# CC2652RMCURadio.net
KiCad netlist of a schematic drawn in Altium Designer
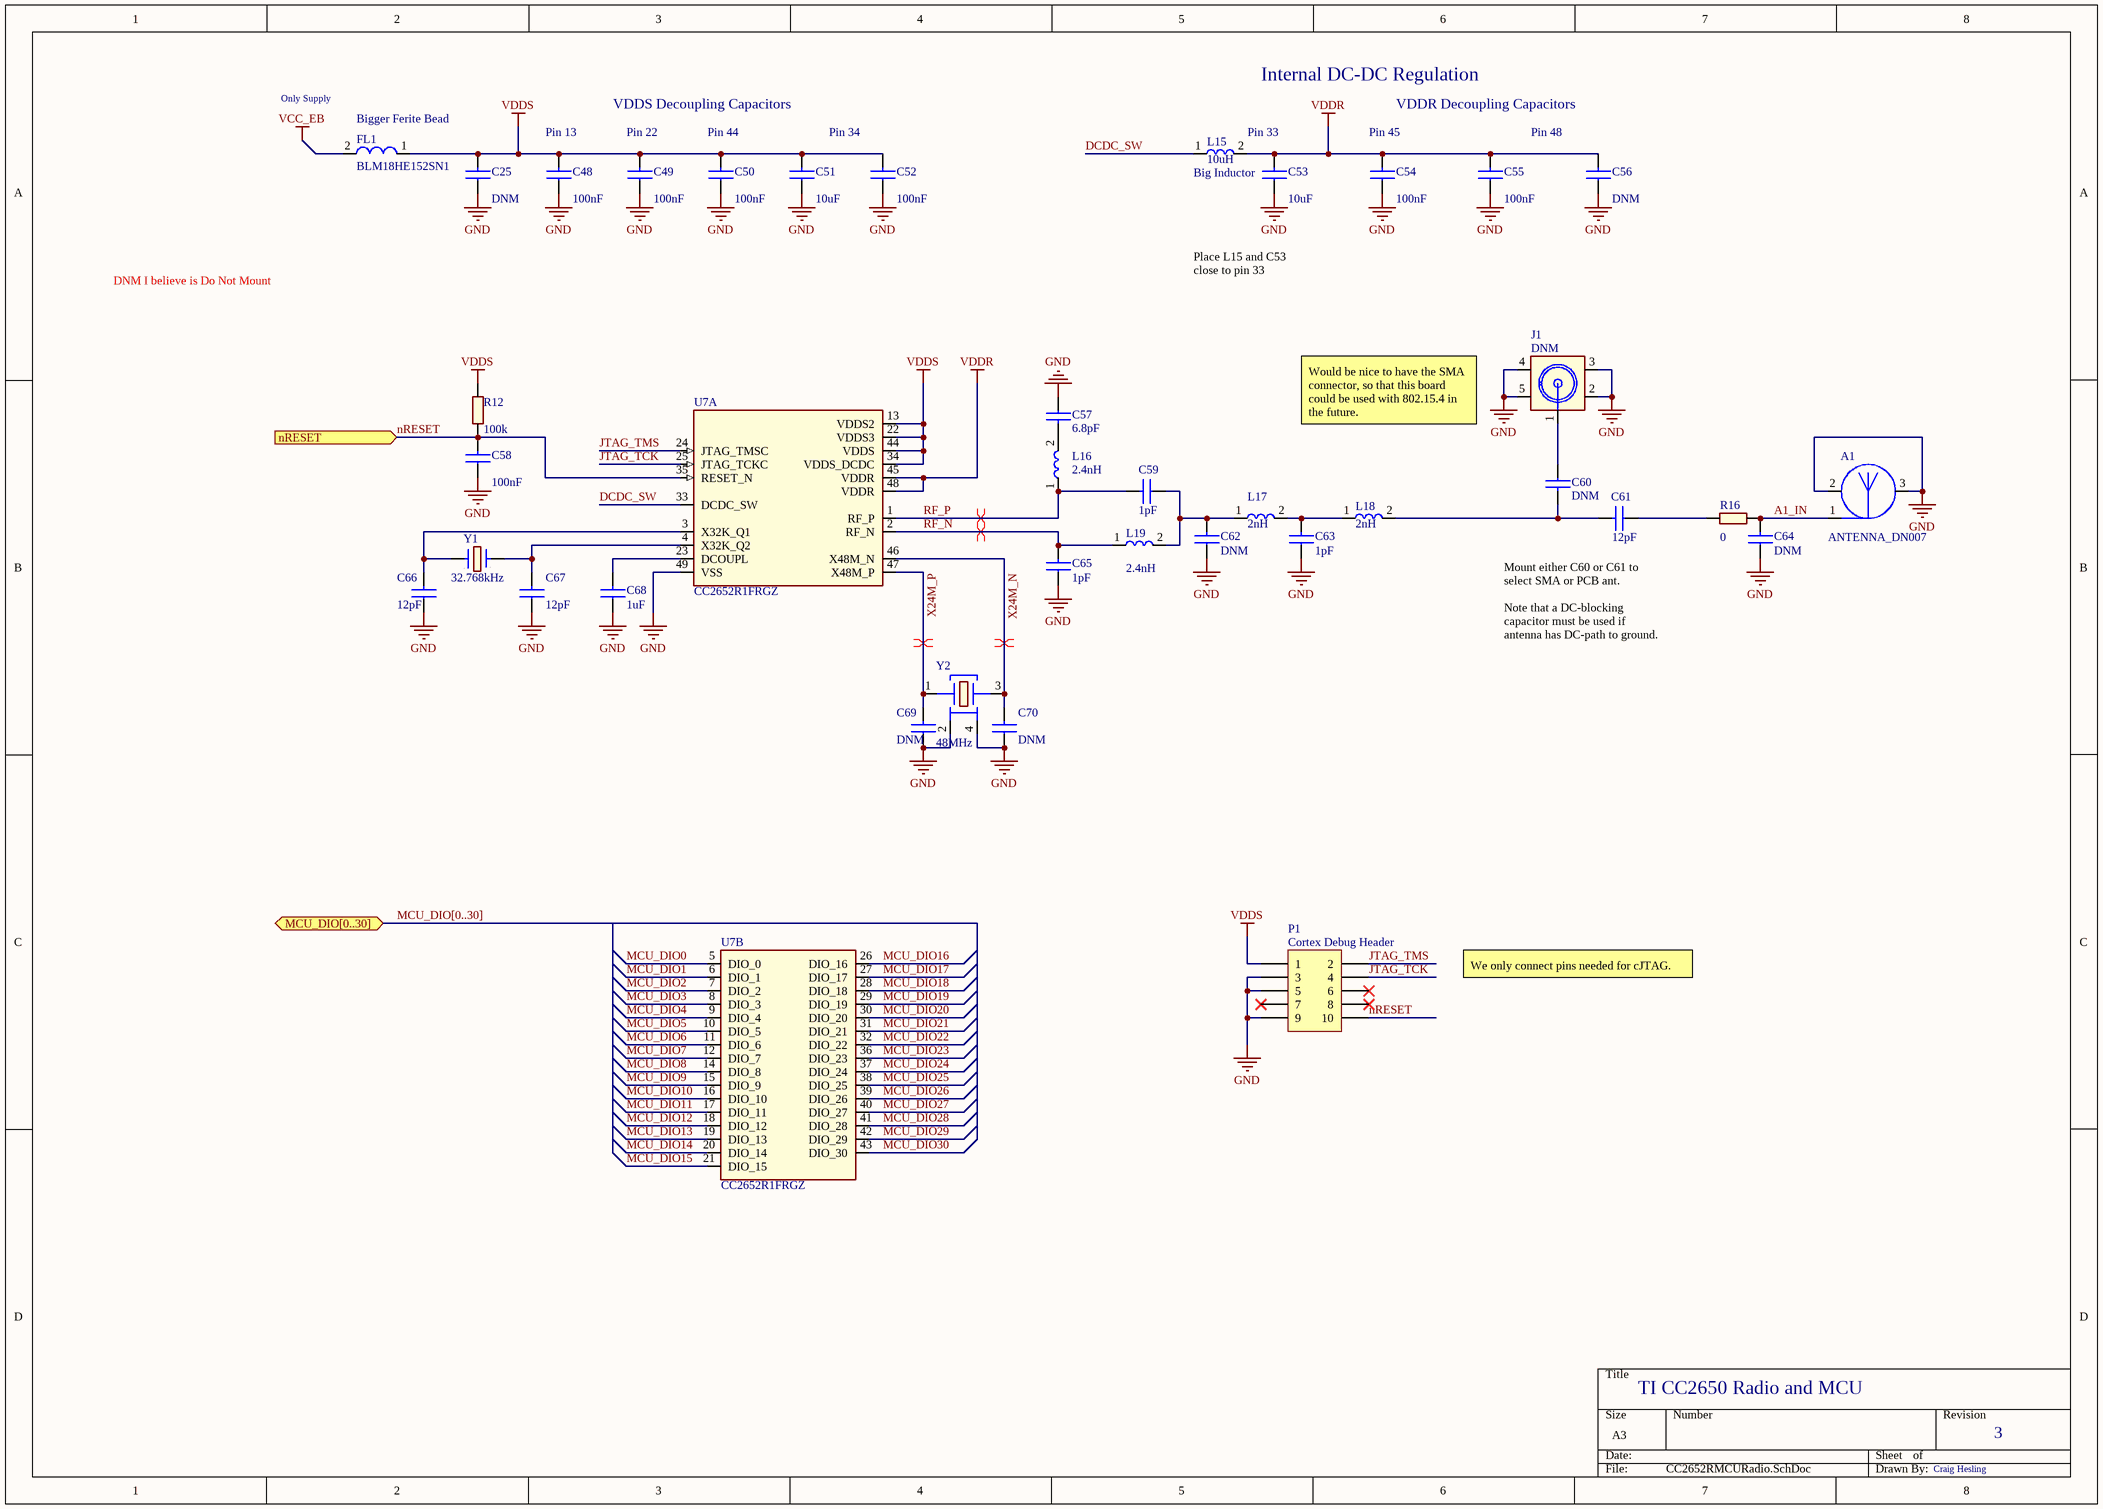
[diagram p0: CC2652RMCURadio.SchDoc]

(export (version "E")
  (design (tool "Eeschema 10.0.6"))
  (components
    (comp (ref "A1")
      (value "ANTENNA_DN007")
      (footprint "ANTENNA_DN007AN_NO_MASK")
      (fields (field (name "DESIGNED BY") "Artur Bielinski"))
      (libsource (lib "CC26XX_7X7_DIFF_Library") (part "ANTENNA_DN007"))
    )
    (comp (ref "C25")
      (value "DNM")
      (footprint "CAPC0402(1005)60_N")
      (fields (field (name "VOLTAGE") "CMAX") (field (name "Comment") "CAPACITOR"))
      (libsource (lib "CC26XX_7X7_DIFF_Library") (part "CAPACITOR"))
    )
    (comp (ref "C48")
      (value "100nF")
      (footprint "CAPC0402(1005)60_N")
      (fields (field (name "VOLTAGE") "CMAX") (field (name "Comment") "CAPACITOR"))
      (libsource (lib "CC26XX_7X7_DIFF_Library") (part "CAPACITOR"))
    )
    (comp (ref "C49")
      (value "100nF")
      (footprint "CAPC0402(1005)60_N")
      (fields (field (name "VOLTAGE") "CMAX") (field (name "Comment") "CAPACITOR"))
      (libsource (lib "CC26XX_7X7_DIFF_Library") (part "CAPACITOR"))
    )
    (comp (ref "C50")
      (value "100nF")
      (footprint "CAPC0402(1005)60_N")
      (fields (field (name "VOLTAGE") "CMAX") (field (name "Comment") "CAPACITOR"))
      (libsource (lib "CC26XX_7X7_DIFF_Library") (part "CAPACITOR"))
    )
    (comp (ref "C51")
      (value "10uF")
      (footprint "CAPC0603(1608)100_N")
      (fields (field (name "VOLTAGE") "CMAX") (field (name "Comment") "CAPACITOR"))
      (libsource (lib "CC26XX_7X7_DIFF_Library") (part "CAPACITOR"))
    )
    (comp (ref "C52")
      (value "100nF")
      (footprint "CAPC0603(1608)100_N")
      (fields (field (name "VOLTAGE") "CMAX") (field (name "Comment") "CAPACITOR"))
      (libsource (lib "CC26XX_7X7_DIFF_Library") (part "CAPACITOR"))
    )
    (comp (ref "C53")
      (value "10uF")
      (footprint "CAPC0603(1608)100_N")
      (fields (field (name "VOLTAGE") "CMAX") (field (name "Comment") "CAPACITOR"))
      (libsource (lib "CC26XX_7X7_DIFF_Library") (part "CAPACITOR"))
    )
    (comp (ref "C54")
      (value "100nF")
      (footprint "CAPC0402(1005)60_N")
      (fields (field (name "VOLTAGE") "CMAX") (field (name "Comment") "CAPACITOR"))
      (libsource (lib "CC26XX_7X7_DIFF_Library") (part "CAPACITOR"))
    )
    (comp (ref "C55")
      (value "100nF")
      (footprint "CAPC0402(1005)60_N")
      (fields (field (name "VOLTAGE") "CMAX") (field (name "Comment") "CAPACITOR"))
      (libsource (lib "CC26XX_7X7_DIFF_Library") (part "CAPACITOR"))
    )
    (comp (ref "C56")
      (value "DNM")
      (footprint "CAPC0402(1005)60_N")
      (fields (field (name "VOLTAGE") "CMAX") (field (name "Comment") "CAPACITOR"))
      (libsource (lib "CC26XX_7X7_DIFF_Library") (part "CAPACITOR"))
    )
    (comp (ref "C57")
      (value "6.8pF")
      (footprint "CAPC0402(1005)60_N")
      (fields (field (name "VOLTAGE") "CMAX") (field (name "Comment") "CAPACITOR"))
      (libsource (lib "CC26XX_7X7_DIFF_Library") (part "CAPACITOR"))
    )
    (comp (ref "C58")
      (value "100nF")
      (footprint "CAPC0402(1005)60_N")
      (fields (field (name "VOLTAGE") "CMAX") (field (name "Comment") "CAPACITOR"))
      (libsource (lib "CC26XX_7X7_DIFF_Library") (part "CAPACITOR"))
    )
    (comp (ref "C59")
      (value "1pF")
      (footprint "CAPC0402(1005)60_N")
      (fields (field (name "VOLTAGE") "CMAX") (field (name "Comment") "CAPACITOR"))
      (libsource (lib "CC26XX_7X7_DIFF_Library") (part "CAPACITOR"))
    )
    (comp (ref "C60")
      (value "DNM")
      (footprint "CAPC0402(1005)60_N")
      (fields (field (name "VOLTAGE") "CMAX") (field (name "Comment") "CAPACITOR"))
      (libsource (lib "CC26XX_7X7_DIFF_Library") (part "CAPACITOR"))
    )
    (comp (ref "C61")
      (value "12pF")
      (footprint "CAPC0402(1005)60_N")
      (fields (field (name "VOLTAGE") "CMAX") (field (name "Comment") "CAPACITOR"))
      (libsource (lib "CC26XX_7X7_DIFF_Library") (part "CAPACITOR"))
    )
    (comp (ref "C62")
      (value "DNM")
      (footprint "CAPC0402(1005)60_N")
      (fields (field (name "VOLTAGE") "CMAX") (field (name "Comment") "CAPACITOR"))
      (libsource (lib "CC26XX_7X7_DIFF_Library") (part "CAPACITOR"))
    )
    (comp (ref "C63")
      (value "1pF")
      (footprint "CAPC0402(1005)60_N")
      (fields (field (name "VOLTAGE") "CMAX") (field (name "Comment") "CAPACITOR"))
      (libsource (lib "CC26XX_7X7_DIFF_Library") (part "CAPACITOR"))
    )
    (comp (ref "C64")
      (value "DNM")
      (footprint "CAPC0402(1005)60_N")
      (fields (field (name "VOLTAGE") "CMAX") (field (name "Comment") "CAPACITOR"))
      (libsource (lib "CC26XX_7X7_DIFF_Library") (part "CAPACITOR"))
    )
    (comp (ref "C65")
      (value "1pF")
      (footprint "CAPC0402(1005)60_N")
      (fields (field (name "VOLTAGE") "CMAX") (field (name "Comment") "CAPACITOR"))
      (libsource (lib "CC26XX_7X7_DIFF_Library") (part "CAPACITOR"))
    )
    (comp (ref "C66")
      (value "12pF")
      (footprint "CAPC0402(1005)60_N")
      (fields (field (name "VOLTAGE") "CMAX") (field (name "Comment") "CAPACITOR"))
      (libsource (lib "CC26XX_7X7_DIFF_Library") (part "CAPACITOR"))
    )
    (comp (ref "C67")
      (value "12pF")
      (footprint "CAPC0402(1005)60_N")
      (fields (field (name "VOLTAGE") "CMAX") (field (name "Comment") "CAPACITOR"))
      (libsource (lib "CC26XX_7X7_DIFF_Library") (part "CAPACITOR"))
    )
    (comp (ref "C68")
      (value "1uF")
      (footprint "CAPC0402(1005)60_N")
      (fields (field (name "VOLTAGE") "CMAX") (field (name "Comment") "CAPACITOR"))
      (libsource (lib "CC26XX_7X7_DIFF_Library") (part "CAPACITOR"))
    )
    (comp (ref "C69")
      (value "DNM")
      (footprint "CAPC0402(1005)60_N")
      (fields (field (name "VOLTAGE") "CMAX") (field (name "Comment") "CAPACITOR"))
      (libsource (lib "CC26XX_7X7_DIFF_Library") (part "CAPACITOR"))
    )
    (comp (ref "C70")
      (value "DNM")
      (footprint "CAPC0402(1005)60_N")
      (fields (field (name "VOLTAGE") "CMAX") (field (name "Comment") "CAPACITOR"))
      (libsource (lib "CC26XX_7X7_DIFF_Library") (part "CAPACITOR"))
    )
    (comp (ref "FL1")
      (value "BLM18HE152SN1")
      (footprint "FIL_BLM18HE152SN1DL")
      (libsource (lib "CC26XX_7X7_DIFF_Library") (part "FILTER_2PIN"))
    )
    (comp (ref "J1")
      (value "DNM")
      (footprint "HUSTSAN_SMA10V21TGGAN_POLYGONPOUR_CUTOUT")
      (libsource (lib "CC26XX_7X7_DIFF_Library") (part "CONN_COAX_1+4"))
    )
    (comp (ref "L15")
      (value "10uH")
      (footprint "CAPC0805(2012)75_N")
      (fields (field (name "Comment") "INDUCTOR"))
      (libsource (lib "CC26XX_7X7_DIFF_Library") (part "INDUCTOR"))
    )
    (comp (ref "L16")
      (value "2.4nH")
      (footprint "INDC1005X60L")
      (fields (field (name "Comment") "INDUCTOR"))
      (libsource (lib "CC26XX_7X7_DIFF_Library") (part "INDUCTOR"))
    )
    (comp (ref "L17")
      (value "2nH")
      (footprint "INDC1005X60L")
      (fields (field (name "Comment") "INDUCTOR"))
      (libsource (lib "CC26XX_7X7_DIFF_Library") (part "INDUCTOR"))
    )
    (comp (ref "L18")
      (value "2nH")
      (footprint "INDC1005X60L")
      (fields (field (name "Comment") "INDUCTOR"))
      (libsource (lib "CC26XX_7X7_DIFF_Library") (part "INDUCTOR"))
    )
    (comp (ref "L19")
      (value "2.4nH")
      (footprint "INDC1005X60L")
      (fields (field (name "Comment") "INDUCTOR"))
      (libsource (lib "CC26XX_7X7_DIFF_Library") (part "INDUCTOR"))
    )
    (comp (ref "P1")
      (value "Cortex Debug Header")
      (footprint "Header 1.27mm 2x5 SMT Low-Profile")
      (description "Header 1.27mm 5X2 SMT Low-Profile")
      (fields (field (name "PUBLISHER") "Altium Limited"))
      (libsource (lib "Connectors") (part "Header 1.27mm 5X2 SMT Low-Profile"))
    )
    (comp (ref "R12")
      (value "100k")
      (footprint "RESC1005X40L")
      (fields
        (field (name "VOLTAGE") "RVMAX")
        (field (name "POWER") "RMAX")
        (field (name "Comment") "RESISTOR")
      )
      (libsource (lib "CC26XX_7X7_DIFF_Library") (part "RESISTOR"))
    )
    (comp (ref "R16")
      (value "0")
      (footprint "RESC1005X40L")
      (fields
        (field (name "VOLTAGE") "RVMAX")
        (field (name "POWER") "RMAX")
        (field (name "Comment") "RESISTOR")
      )
      (libsource (lib "") (part "RESISTOR_1"))
    )
    (comp (ref "U7")
      (value "CC2652R1FRGZ")
      (footprint "QFN50P700X700X100_HS-49N")
      (fields (field (name "PARTNUMBER") "CC2650F128RGZT") (field (name "DESIGNED_BY") "Artur Bielinski"))
      (libsource (lib "lib") (part "CC2652R1FRGZ"))
    )
    (comp (ref "Y1")
      (value "CRYSTAL")
      (footprint "XTAL_FC-135N")
      (fields (field (name "FREQUENCY") "32.768kHz"))
      (libsource (lib "CC26XX_7X7_DIFF_Library") (part "CRYSTAL"))
    )
    (comp (ref "Y2")
      (value "CX2016DB48000C0FPLC1")
      (footprint "Crystal 4-SMD 2.0MMx1.6MM")
      (description "Crystal 48MHz")
      (fields (field (name "PARTNUMBER") "ABM3B-24.000MHZ-10-1-U-T") (field (name "FREQUENCY") "48MHz"))
      (libsource (lib "lib") (part "XTAL_4PIN_S_1"))
    )
  )
  (nets
    (net (code "1") (name "/A1_IN") (class "Default")
      (node (ref "A1") (pin "1") (pinfunction "FEED_1_1") (pintype "passive"))
      (node (ref "C64") (pin "2") (pinfunction "2_2") (pintype "passive"))
      (node (ref "R16") (pin "1") (pinfunction "1_1") (pintype "passive"))
    )
    (net (code "2") (name "/DCDC_SW") (class "Default")
      (node (ref "L15") (pin "1") (pinfunction "1_1") (pintype "passive"))
      (node (ref "U7") (pin "33") (pinfunction "DCDC_SW_33") (pintype "power_in"))
    )
    (net (code "3") (name "/JTAG_TCK") (class "Default")
      (node (ref "P1") (pin "4") (pinfunction "4_4") (pintype "passive"))
      (node (ref "U7") (pin "25") (pinfunction "JTAG_TCKC_25") (pintype "input"))
    )
    (net (code "4") (name "/JTAG_TMS") (class "Default")
      (node (ref "P1") (pin "2") (pinfunction "2_2") (pintype "passive"))
      (node (ref "U7") (pin "24") (pinfunction "JTAG_TMSC_24") (pintype "input"))
    )
    (net (code "5") (name "/MCU_DIO0") (class "Default")
      (node (ref "U7") (pin "5") (pinfunction "DIO_0_5") (pintype "bidirectional"))
    )
    (net (code "6") (name "/MCU_DIO1") (class "Default")
      (node (ref "U7") (pin "6") (pinfunction "DIO_1_6") (pintype "bidirectional"))
    )
    (net (code "7") (name "/MCU_DIO2") (class "Default")
      (node (ref "U7") (pin "7") (pinfunction "DIO_2_7") (pintype "bidirectional"))
    )
    (net (code "8") (name "/MCU_DIO3") (class "Default")
      (node (ref "U7") (pin "8") (pinfunction "DIO_3_8") (pintype "bidirectional"))
    )
    (net (code "9") (name "/MCU_DIO4") (class "Default")
      (node (ref "U7") (pin "9") (pinfunction "DIO_4_9") (pintype "bidirectional"))
    )
    (net (code "10") (name "/MCU_DIO5") (class "Default")
      (node (ref "U7") (pin "10") (pinfunction "DIO_5_10") (pintype "bidirectional"))
    )
    (net (code "11") (name "/MCU_DIO6") (class "Default")
      (node (ref "U7") (pin "11") (pinfunction "DIO_6_11") (pintype "bidirectional"))
    )
    (net (code "12") (name "/MCU_DIO7") (class "Default")
      (node (ref "U7") (pin "12") (pinfunction "DIO_7_12") (pintype "bidirectional"))
    )
    (net (code "13") (name "/MCU_DIO8") (class "Default")
      (node (ref "U7") (pin "14") (pinfunction "DIO_8_14") (pintype "bidirectional"))
    )
    (net (code "14") (name "/MCU_DIO9") (class "Default")
      (node (ref "U7") (pin "15") (pinfunction "DIO_9_15") (pintype "bidirectional"))
    )
    (net (code "15") (name "/MCU_DIO10") (class "Default")
      (node (ref "U7") (pin "16") (pinfunction "DIO_10_16") (pintype "bidirectional"))
    )
    (net (code "16") (name "/MCU_DIO11") (class "Default")
      (node (ref "U7") (pin "17") (pinfunction "DIO_11_17") (pintype "bidirectional"))
    )
    (net (code "17") (name "/MCU_DIO12") (class "Default")
      (node (ref "U7") (pin "18") (pinfunction "DIO_12_18") (pintype "bidirectional"))
    )
    (net (code "18") (name "/MCU_DIO13") (class "Default")
      (node (ref "U7") (pin "19") (pinfunction "DIO_13_19") (pintype "bidirectional"))
    )
    (net (code "19") (name "/MCU_DIO14") (class "Default")
      (node (ref "U7") (pin "20") (pinfunction "DIO_14_20") (pintype "bidirectional"))
    )
    (net (code "20") (name "/MCU_DIO15") (class "Default")
      (node (ref "U7") (pin "21") (pinfunction "DIO_15_21") (pintype "bidirectional"))
    )
    (net (code "21") (name "/MCU_DIO16") (class "Default")
      (node (ref "U7") (pin "26") (pinfunction "DIO_16_26") (pintype "bidirectional"))
    )
    (net (code "22") (name "/MCU_DIO17") (class "Default")
      (node (ref "U7") (pin "27") (pinfunction "DIO_17_27") (pintype "bidirectional"))
    )
    (net (code "23") (name "/MCU_DIO18") (class "Default")
      (node (ref "U7") (pin "28") (pinfunction "DIO_18_28") (pintype "bidirectional"))
    )
    (net (code "24") (name "/MCU_DIO19") (class "Default")
      (node (ref "U7") (pin "29") (pinfunction "DIO_19_29") (pintype "bidirectional"))
    )
    (net (code "25") (name "/MCU_DIO20") (class "Default")
      (node (ref "U7") (pin "30") (pinfunction "DIO_20_30") (pintype "bidirectional"))
    )
    (net (code "26") (name "/MCU_DIO21") (class "Default")
      (node (ref "U7") (pin "31") (pinfunction "DIO_21_31") (pintype "bidirectional"))
    )
    (net (code "27") (name "/MCU_DIO22") (class "Default")
      (node (ref "U7") (pin "32") (pinfunction "DIO_22_32") (pintype "bidirectional"))
    )
    (net (code "28") (name "/MCU_DIO23") (class "Default")
      (node (ref "U7") (pin "36") (pinfunction "DIO_23_36") (pintype "bidirectional"))
    )
    (net (code "29") (name "/MCU_DIO24") (class "Default")
      (node (ref "U7") (pin "37") (pinfunction "DIO_24_37") (pintype "bidirectional"))
    )
    (net (code "30") (name "/MCU_DIO25") (class "Default")
      (node (ref "U7") (pin "38") (pinfunction "DIO_25_38") (pintype "bidirectional"))
    )
    (net (code "31") (name "/MCU_DIO26") (class "Default")
      (node (ref "U7") (pin "39") (pinfunction "DIO_26_39") (pintype "bidirectional"))
    )
    (net (code "32") (name "/MCU_DIO27") (class "Default")
      (node (ref "U7") (pin "40") (pinfunction "DIO_27_40") (pintype "bidirectional"))
    )
    (net (code "33") (name "/MCU_DIO28") (class "Default")
      (node (ref "U7") (pin "41") (pinfunction "DIO_28_41") (pintype "bidirectional"))
    )
    (net (code "34") (name "/MCU_DIO29") (class "Default")
      (node (ref "U7") (pin "42") (pinfunction "DIO_29_42") (pintype "bidirectional"))
    )
    (net (code "35") (name "/MCU_DIO30") (class "Default")
      (node (ref "U7") (pin "43") (pinfunction "DIO_30_43") (pintype "bidirectional"))
    )
    (net (code "37") (name "/RF_N") (class "Default")
      (node (ref "C65") (pin "2") (pinfunction "2_2") (pintype "passive"))
      (node (ref "L19") (pin "1") (pinfunction "1_1") (pintype "passive"))
      (node (ref "U7") (pin "2") (pinfunction "RF_N_2") (pintype "passive"))
    )
    (net (code "38") (name "/RF_P") (class "Default")
      (node (ref "C59") (pin "2") (pinfunction "2_2") (pintype "passive"))
      (node (ref "L16") (pin "1") (pinfunction "1_1") (pintype "passive"))
      (node (ref "U7") (pin "1") (pinfunction "RF_P_1") (pintype "passive"))
    )
    (net (code "39") (name "/X24M_N") (class "Default")
      (node (ref "C70") (pin "2") (pinfunction "2_2") (pintype "passive"))
      (node (ref "U7") (pin "46") (pinfunction "X48M_N_46") (pintype "passive"))
      (node (ref "Y2") (pin "3") (pinfunction "3_3") (pintype "passive"))
    )
    (net (code "40") (name "/X24M_P") (class "Default")
      (node (ref "C69") (pin "2") (pinfunction "2_2") (pintype "passive"))
      (node (ref "U7") (pin "47") (pinfunction "X48M_P_47") (pintype "passive"))
      (node (ref "Y2") (pin "1") (pinfunction "1_1") (pintype "passive"))
    )
    (net (code "41") (name "/nRESET") (class "Default")
      (node (ref "C58") (pin "2") (pinfunction "2_2") (pintype "passive"))
      (node (ref "P1") (pin "10") (pinfunction "10_10") (pintype "passive"))
      (node (ref "R12") (pin "1") (pinfunction "1_1") (pintype "passive"))
      (node (ref "U7") (pin "35") (pinfunction "RESET_N_35") (pintype "input"))
    )
    (net (code "42") (name "GND") (class "Default")
      (node (ref "A1") (pin "2") (pinfunction "GND_2_2") (pintype "passive"))
      (node (ref "A1") (pin "3") (pinfunction "GND_3_3") (pintype "passive"))
      (node (ref "C25") (pin "1") (pinfunction "1_1") (pintype "passive"))
      (node (ref "C48") (pin "1") (pinfunction "1_1") (pintype "passive"))
      (node (ref "C49") (pin "1") (pinfunction "1_1") (pintype "passive"))
      (node (ref "C50") (pin "1") (pinfunction "1_1") (pintype "passive"))
      (node (ref "C51") (pin "1") (pinfunction "1_1") (pintype "passive"))
      (node (ref "C52") (pin "1") (pinfunction "1_1") (pintype "passive"))
      (node (ref "C53") (pin "1") (pinfunction "1_1") (pintype "passive"))
      (node (ref "C54") (pin "1") (pinfunction "1_1") (pintype "passive"))
      (node (ref "C55") (pin "1") (pinfunction "1_1") (pintype "passive"))
      (node (ref "C56") (pin "1") (pinfunction "1_1") (pintype "passive"))
      (node (ref "C57") (pin "1") (pinfunction "1_1") (pintype "passive"))
      (node (ref "C58") (pin "1") (pinfunction "1_1") (pintype "passive"))
      (node (ref "C62") (pin "1") (pinfunction "1_1") (pintype "passive"))
      (node (ref "C63") (pin "1") (pinfunction "1_1") (pintype "passive"))
      (node (ref "C64") (pin "1") (pinfunction "1_1") (pintype "passive"))
      (node (ref "C65") (pin "1") (pinfunction "1_1") (pintype "passive"))
      (node (ref "C66") (pin "1") (pinfunction "1_1") (pintype "passive"))
      (node (ref "C67") (pin "1") (pinfunction "1_1") (pintype "passive"))
      (node (ref "C68") (pin "1") (pinfunction "1_1") (pintype "passive"))
      (node (ref "C69") (pin "1") (pinfunction "1_1") (pintype "passive"))
      (node (ref "C70") (pin "1") (pinfunction "1_1") (pintype "passive"))
      (node (ref "J1") (pin "2") (pinfunction "2_2") (pintype "power_in"))
      (node (ref "J1") (pin "3") (pinfunction "3_3") (pintype "power_in"))
      (node (ref "J1") (pin "4") (pinfunction "4_4") (pintype "power_in"))
      (node (ref "J1") (pin "5") (pinfunction "5_5") (pintype "power_in"))
      (node (ref "P1") (pin "3") (pinfunction "3_3") (pintype "passive"))
      (node (ref "P1") (pin "5") (pinfunction "5_5") (pintype "passive"))
      (node (ref "P1") (pin "9") (pinfunction "9_9") (pintype "passive"))
      (node (ref "U7") (pin "49") (pinfunction "VSS_49") (pintype "power_in"))
      (node (ref "Y2") (pin "2") (pinfunction "2_2") (pintype "power_in"))
      (node (ref "Y2") (pin "4") (pinfunction "4_4") (pintype "power_in"))
    )
    (net (code "43") (name "Net-(C57-Pad2)") (class "Default")
      (node (ref "C57") (pin "2") (pinfunction "2_2") (pintype "passive"))
      (node (ref "L16") (pin "2") (pinfunction "2_2") (pintype "passive"))
    )
    (net (code "44") (name "Net-(C59-Pad1)") (class "Default")
      (node (ref "C59") (pin "1") (pinfunction "1_1") (pintype "passive"))
      (node (ref "C62") (pin "2") (pinfunction "2_2") (pintype "passive"))
      (node (ref "L17") (pin "1") (pinfunction "1_1") (pintype "passive"))
      (node (ref "L19") (pin "2") (pinfunction "2_2") (pintype "passive"))
    )
    (net (code "45") (name "Net-(C60-Pad1)") (class "Default")
      (node (ref "C60") (pin "1") (pinfunction "1_1") (pintype "passive"))
      (node (ref "J1") (pin "1") (pinfunction "1_1") (pintype "passive"))
    )
    (net (code "46") (name "Net-(C60-Pad2)") (class "Default")
      (node (ref "C60") (pin "2") (pinfunction "2_2") (pintype "passive"))
      (node (ref "C61") (pin "2") (pinfunction "2_2") (pintype "passive"))
      (node (ref "L18") (pin "2") (pinfunction "2_2") (pintype "passive"))
    )
    (net (code "47") (name "Net-(C61-Pad1)") (class "Default")
      (node (ref "C61") (pin "1") (pinfunction "1_1") (pintype "passive"))
      (node (ref "R16") (pin "2") (pinfunction "2_2") (pintype "passive"))
    )
    (net (code "48") (name "Net-(C63-Pad2)") (class "Default")
      (node (ref "C63") (pin "2") (pinfunction "2_2") (pintype "passive"))
      (node (ref "L17") (pin "2") (pinfunction "2_2") (pintype "passive"))
      (node (ref "L18") (pin "1") (pinfunction "1_1") (pintype "passive"))
    )
    (net (code "49") (name "Net-(U7A-DCOUPL)") (class "Default")
      (node (ref "C68") (pin "2") (pinfunction "2_2") (pintype "passive"))
      (node (ref "U7") (pin "23") (pinfunction "DCOUPL_23") (pintype "passive"))
    )
    (net (code "50") (name "Net-(U7A-X32K_Q1)") (class "Default")
      (node (ref "C66") (pin "2") (pinfunction "2_2") (pintype "passive"))
      (node (ref "U7") (pin "3") (pinfunction "X32K_Q1_3") (pintype "passive"))
      (node (ref "Y1") (pin "1") (pinfunction "1_1") (pintype "passive"))
    )
    (net (code "51") (name "Net-(U7A-X32K_Q2)") (class "Default")
      (node (ref "C67") (pin "2") (pinfunction "2_2") (pintype "passive"))
      (node (ref "U7") (pin "4") (pinfunction "X32K_Q2_4") (pintype "passive"))
      (node (ref "Y1") (pin "2") (pinfunction "2_2") (pintype "passive"))
    )
    (net (code "52") (name "VCC_EB") (class "Default")
      (node (ref "FL1") (pin "2") (pinfunction "2_2") (pintype "passive"))
    )
    (net (code "53") (name "VDDR") (class "Default")
      (node (ref "C53") (pin "2") (pinfunction "2_2") (pintype "passive"))
      (node (ref "C54") (pin "2") (pinfunction "2_2") (pintype "passive"))
      (node (ref "C55") (pin "2") (pinfunction "2_2") (pintype "passive"))
      (node (ref "C56") (pin "2") (pinfunction "2_2") (pintype "passive"))
      (node (ref "L15") (pin "2") (pinfunction "2_2") (pintype "passive"))
      (node (ref "U7") (pin "45") (pinfunction "VDDR_45") (pintype "power_in"))
      (node (ref "U7") (pin "48") (pinfunction "VDDR_48") (pintype "power_in"))
    )
    (net (code "54") (name "VDDS") (class "Default")
      (node (ref "C25") (pin "2") (pinfunction "2_2") (pintype "passive"))
      (node (ref "C48") (pin "2") (pinfunction "2_2") (pintype "passive"))
      (node (ref "C49") (pin "2") (pinfunction "2_2") (pintype "passive"))
      (node (ref "C50") (pin "2") (pinfunction "2_2") (pintype "passive"))
      (node (ref "C51") (pin "2") (pinfunction "2_2") (pintype "passive"))
      (node (ref "C52") (pin "2") (pinfunction "2_2") (pintype "passive"))
      (node (ref "FL1") (pin "1") (pinfunction "1_1") (pintype "passive"))
      (node (ref "P1") (pin "1") (pinfunction "1_1") (pintype "passive"))
      (node (ref "R12") (pin "2") (pinfunction "2_2") (pintype "passive"))
      (node (ref "U7") (pin "13") (pinfunction "VDDS2_13") (pintype "power_in"))
      (node (ref "U7") (pin "22") (pinfunction "VDDS3_22") (pintype "power_in"))
      (node (ref "U7") (pin "34") (pinfunction "VDDS_DCDC_34") (pintype "power_in"))
      (node (ref "U7") (pin "44") (pinfunction "VDDS_44") (pintype "power_in"))
    )
    (net (code "55") (name "unconnected-(P1-Pad6)") (class "Default")
      (node (ref "P1") (pin "6") (pinfunction "6_6") (pintype "passive+no_connect"))
    )
    (net (code "56") (name "unconnected-(P1-Pad7)") (class "Default")
      (node (ref "P1") (pin "7") (pinfunction "7_7") (pintype "passive+no_connect"))
    )
    (net (code "57") (name "unconnected-(P1-Pad8)") (class "Default")
      (node (ref "P1") (pin "8") (pinfunction "8_8") (pintype "passive+no_connect"))
    )
  )
)
